# mother_card_19.net
KiCad netlist of a schematic drawn in EAGLE
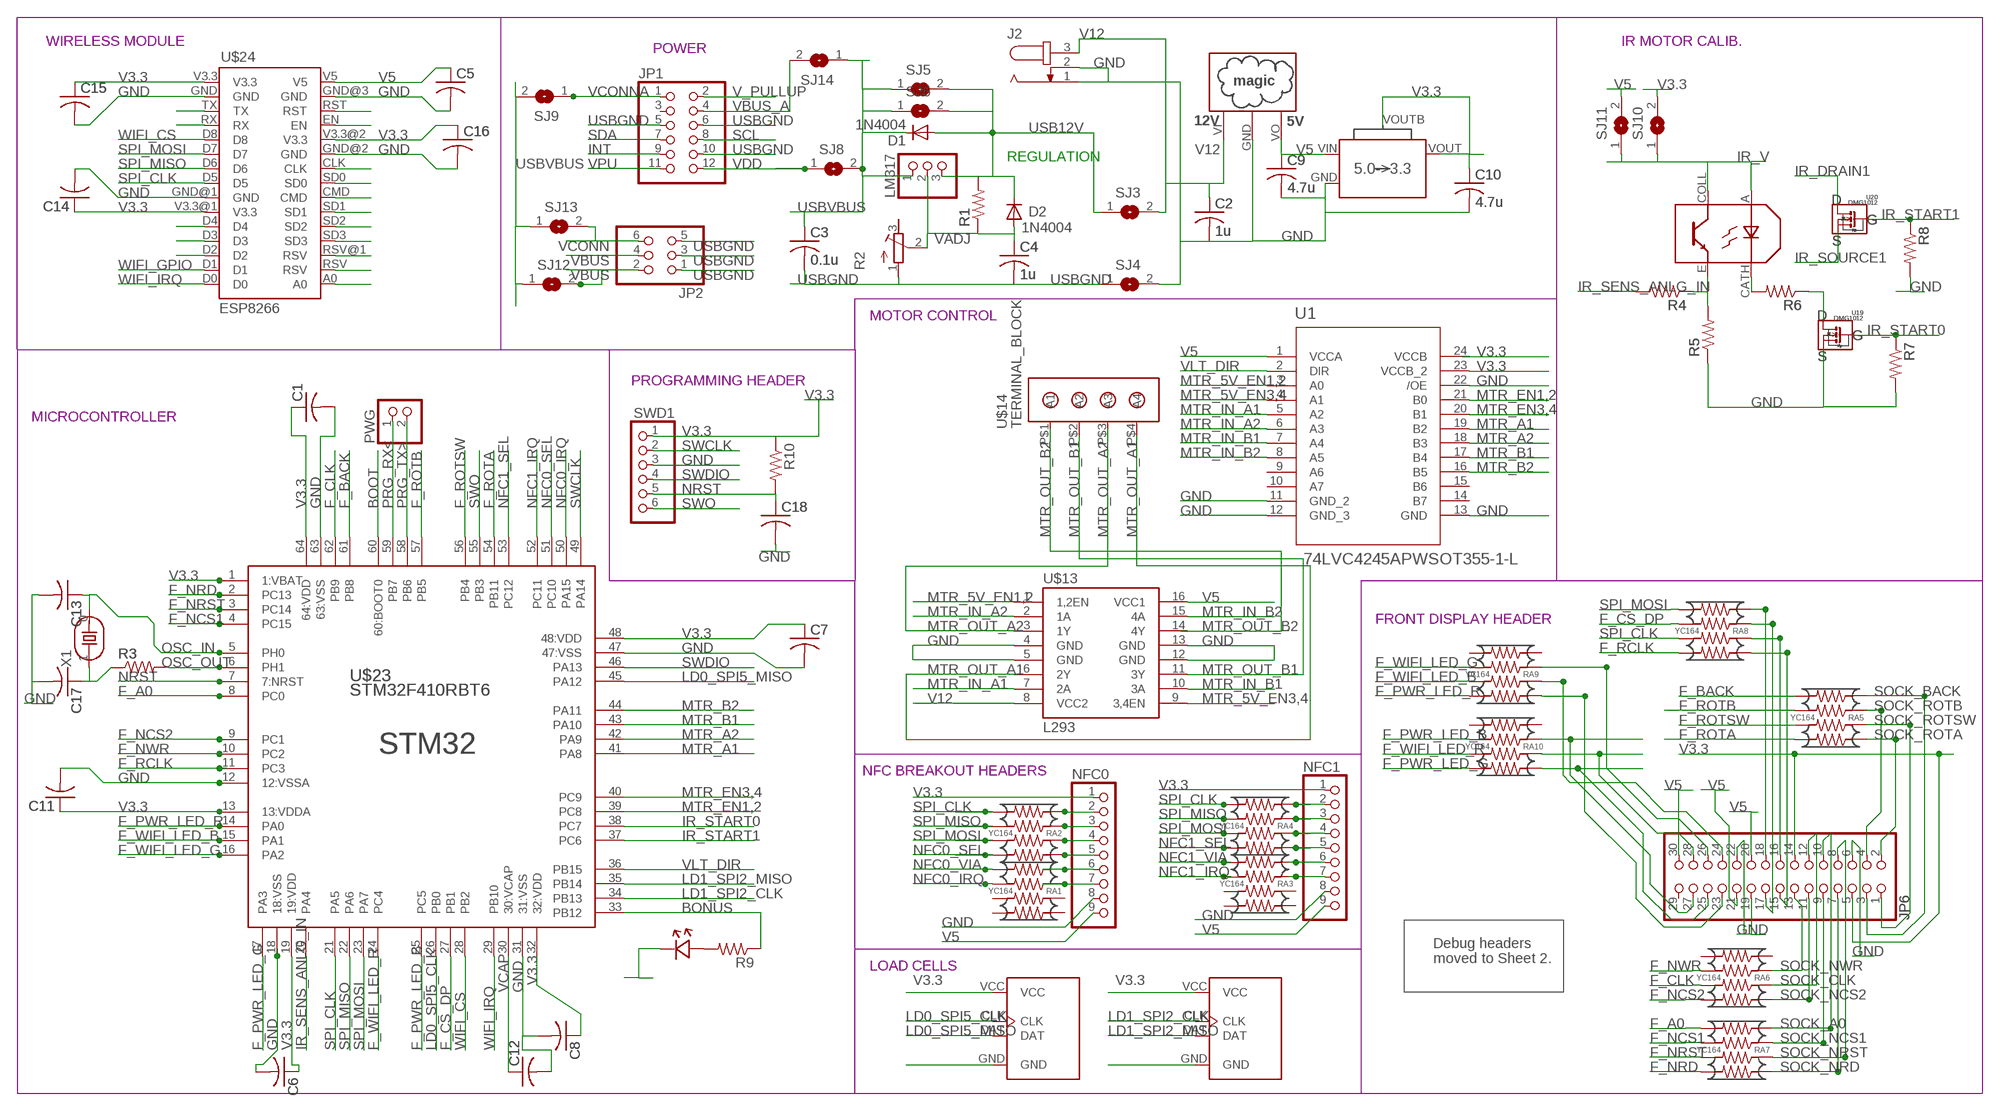
[diagram p0: schematic, sheet 1]
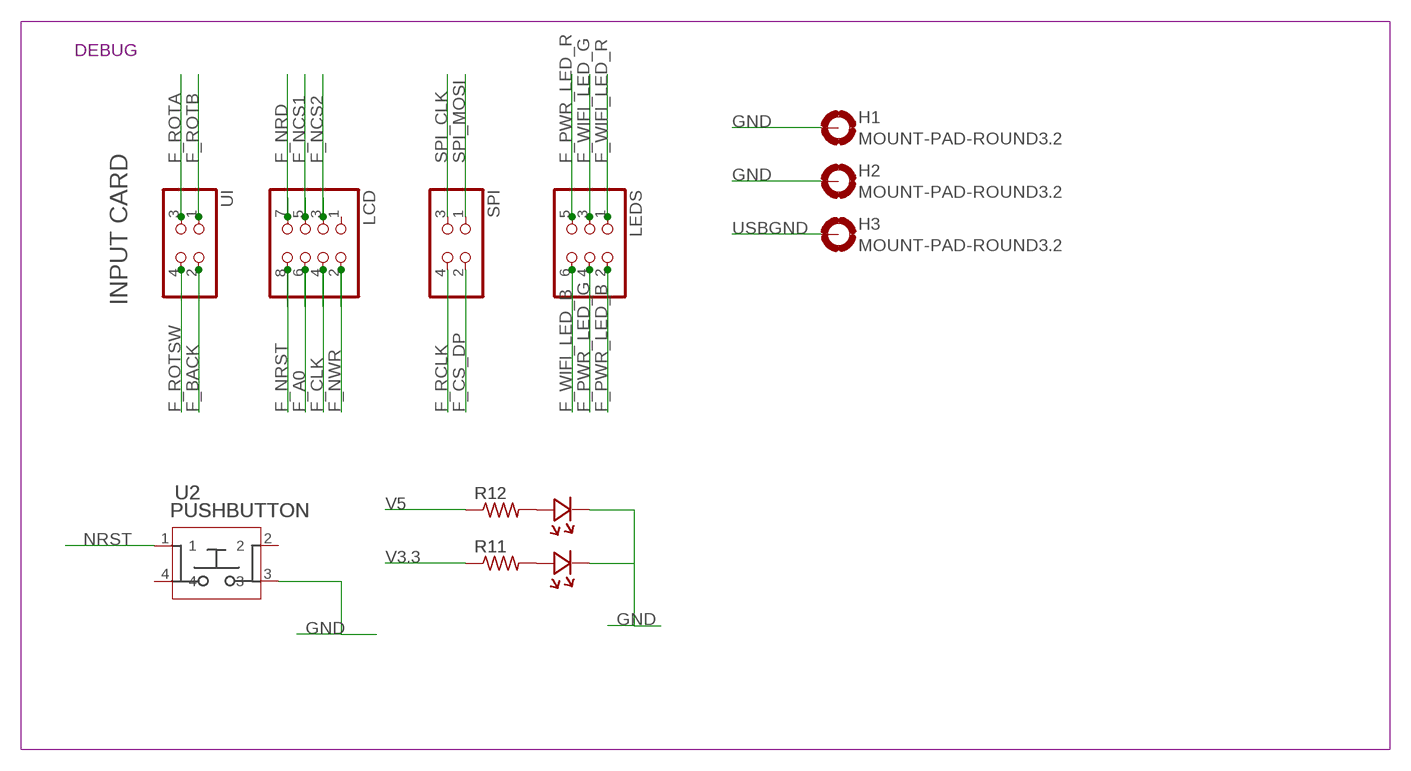
[diagram p1: schematic, sheet 2]

(export (version "E")
  (design (tool "Eeschema 10.0.6"))
  (components
    (comp (ref "C1")
      (value "C-USC0805")
      (footprint "eagle-import:C0805")
      (libsource (lib "eagle-import") (part "C-USC0805"))
    )
    (comp (ref "C2")
      (value "1u")
      (footprint "eagle-import:C0805")
      (libsource (lib "eagle-import") (part "C-USC0805"))
    )
    (comp (ref "C3")
      (value "0.1u")
      (footprint "eagle-import:C0805")
      (libsource (lib "eagle-import") (part "C-USC0805"))
    )
    (comp (ref "C4")
      (value "1u")
      (footprint "eagle-import:C0805")
      (libsource (lib "eagle-import") (part "C-USC0805"))
    )
    (comp (ref "C5")
      (value "C-USC0805")
      (footprint "eagle-import:C0805")
      (libsource (lib "eagle-import") (part "C-USC0805"))
    )
    (comp (ref "C6")
      (value "C-USC0805")
      (footprint "eagle-import:C0805")
      (libsource (lib "eagle-import") (part "C-USC0805"))
    )
    (comp (ref "C7")
      (value "C-USC0805")
      (footprint "eagle-import:C0805")
      (libsource (lib "eagle-import") (part "C-USC0805"))
    )
    (comp (ref "C8")
      (value "C-USC0805")
      (footprint "eagle-import:C0805")
      (libsource (lib "eagle-import") (part "C-USC0805"))
    )
    (comp (ref "C9")
      (value "4.7u")
      (footprint "eagle-import:C0805")
      (libsource (lib "eagle-import") (part "C-USC0805"))
    )
    (comp (ref "C10")
      (value "4.7u")
      (footprint "eagle-import:C0805")
      (libsource (lib "eagle-import") (part "C-USC0805"))
    )
    (comp (ref "C11")
      (value "C-USC0805")
      (footprint "eagle-import:C0805")
      (libsource (lib "eagle-import") (part "C-USC0805"))
    )
    (comp (ref "C12")
      (value "C-USC0805")
      (footprint "eagle-import:C0805")
      (libsource (lib "eagle-import") (part "C-USC0805"))
    )
    (comp (ref "C13")
      (value "C-USC0603")
      (footprint "eagle-import:C0603")
      (libsource (lib "eagle-import") (part "C-USC0603"))
    )
    (comp (ref "C14")
      (value "C-USC0805")
      (footprint "eagle-import:C0805")
      (libsource (lib "eagle-import") (part "C-USC0805"))
    )
    (comp (ref "C15")
      (value "C-USC0805")
      (footprint "eagle-import:C0805")
      (libsource (lib "eagle-import") (part "C-USC0805"))
    )
    (comp (ref "C16")
      (value "C-USC0805")
      (footprint "eagle-import:C0805")
      (libsource (lib "eagle-import") (part "C-USC0805"))
    )
    (comp (ref "C17")
      (value "C-USC0603")
      (footprint "eagle-import:C0603")
      (libsource (lib "eagle-import") (part "C-USC0603"))
    )
    (comp (ref "C18")
      (value "C-USC0805")
      (footprint "eagle-import:C0805")
      (libsource (lib "eagle-import") (part "C-USC0805"))
    )
    (comp (ref "D1")
      (value "1N4004")
      (footprint "eagle-import:DO41-10")
      (libsource (lib "eagle-import") (part "1N4004"))
    )
    (comp (ref "D2")
      (value "1N4004")
      (footprint "eagle-import:DO41-10")
      (libsource (lib "eagle-import") (part "1N4004"))
    )
    (comp (ref "IRSENS")
      (value "TCRT5000")
      (footprint "eagle-import:TCRT5000")
      (libsource (lib "eagle-import") (part "TCRT5000"))
    )
    (comp (ref "J2")
      (value "JACK-PLUG0")
      (footprint "eagle-import:SPC4077")
      (libsource (lib "eagle-import") (part "JACK-PLUG0"))
    )
    (comp (ref "JP1")
      (value "PINHD-2X6")
      (footprint "eagle-import:2X06")
      (libsource (lib "eagle-import") (part "PINHD-2X6"))
    )
    (comp (ref "JP2")
      (value "PINHD-2X3")
      (footprint "eagle-import:2X03")
      (libsource (lib "eagle-import") (part "PINHD-2X3"))
    )
    (comp (ref "JP6")
      (value "PINHD-2X15/SOCK")
      (footprint "eagle-import:2X15_SOCK")
      (libsource (lib "eagle-import") (part "PINHD-2X15/SOCK"))
    )
    (comp (ref "LM317")
      (value "PINHD-1X3")
      (footprint "eagle-import:1X03")
      (libsource (lib "eagle-import") (part "PINHD-1X3"))
    )
    (comp (ref "NFC0")
      (value "PINHD-1X9/90")
      (footprint "eagle-import:1X09_90")
      (libsource (lib "eagle-import") (part "PINHD-1X9/90"))
    )
    (comp (ref "NFC1")
      (value "PINHD-1X9/90")
      (footprint "eagle-import:1X09_90")
      (libsource (lib "eagle-import") (part "PINHD-1X9/90"))
    )
    (comp (ref "PWG")
      (value "PINHD-1X2")
      (footprint "eagle-import:1X02")
      (libsource (lib "eagle-import") (part "PINHD-1X2"))
    )
    (comp (ref "R1")
      (value "R-US_R0805")
      (footprint "eagle-import:R0805")
      (libsource (lib "eagle-import") (part "seniorDesign_R-US_R0805"))
    )
    (comp (ref "R2")
      (value "R-TRIMM64W")
      (footprint "eagle-import:RTRIM64W")
      (libsource (lib "eagle-import") (part "R-TRIMM64W"))
    )
    (comp (ref "R3")
      (value "R-US_R0805")
      (footprint "eagle-import:R0805")
      (libsource (lib "eagle-import") (part "seniorDesign_R-US_R0805"))
    )
    (comp (ref "R4")
      (value "R-US_R0805")
      (footprint "eagle-import:R0805")
      (libsource (lib "eagle-import") (part "seniorDesign_R-US_R0805"))
    )
    (comp (ref "R5")
      (value "R-US_R0805")
      (footprint "eagle-import:R0805")
      (libsource (lib "eagle-import") (part "seniorDesign_R-US_R0805"))
    )
    (comp (ref "R6")
      (value "R-US_R0805")
      (footprint "eagle-import:R0805")
      (libsource (lib "eagle-import") (part "seniorDesign_R-US_R0805"))
    )
    (comp (ref "R7")
      (value "R-US_R0805")
      (footprint "eagle-import:R0805")
      (libsource (lib "eagle-import") (part "seniorDesign_R-US_R0805"))
    )
    (comp (ref "R8")
      (value "R-US_R0805")
      (footprint "eagle-import:R0805")
      (libsource (lib "eagle-import") (part "seniorDesign_R-US_R0805"))
    )
    (comp (ref "R9")
      (value "R-US_R0805")
      (footprint "eagle-import:R0805")
      (libsource (lib "eagle-import") (part "R-US_R0805"))
    )
    (comp (ref "R10")
      (value "R-US_R0805")
      (footprint "eagle-import:R0805")
      (libsource (lib "eagle-import") (part "R-US_R0805"))
    )
    (comp (ref "RA1")
      (value "YC164")
      (footprint "eagle-import:YC164")
      (libsource (lib "eagle-import") (part "YC164"))
    )
    (comp (ref "RA2")
      (value "YC164")
      (footprint "eagle-import:YC164")
      (libsource (lib "eagle-import") (part "YC164"))
    )
    (comp (ref "RA3")
      (value "YC164")
      (footprint "eagle-import:YC164")
      (libsource (lib "eagle-import") (part "YC164"))
    )
    (comp (ref "RA4")
      (value "YC164")
      (footprint "eagle-import:YC164")
      (libsource (lib "eagle-import") (part "YC164"))
    )
    (comp (ref "RA5")
      (value "YC164")
      (footprint "eagle-import:YC164")
      (libsource (lib "eagle-import") (part "YC164"))
    )
    (comp (ref "RA6")
      (value "YC164")
      (footprint "eagle-import:YC164")
      (libsource (lib "eagle-import") (part "YC164"))
    )
    (comp (ref "RA7")
      (value "YC164")
      (footprint "eagle-import:YC164")
      (libsource (lib "eagle-import") (part "YC164"))
    )
    (comp (ref "RA8")
      (value "YC164")
      (footprint "eagle-import:YC164")
      (libsource (lib "eagle-import") (part "YC164"))
    )
    (comp (ref "RA9")
      (value "YC164")
      (footprint "eagle-import:YC164")
      (libsource (lib "eagle-import") (part "YC164"))
    )
    (comp (ref "RA10")
      (value "YC164")
      (footprint "eagle-import:YC164")
      (libsource (lib "eagle-import") (part "YC164"))
    )
    (comp (ref "SJ3") (value "SJ") (footprint "eagle-import:SJ") (libsource (lib "eagle-import") (part "SJ")))
    (comp (ref "SJ4") (value "SJ") (footprint "eagle-import:SJ") (libsource (lib "eagle-import") (part "SJ")))
    (comp (ref "SJ5") (value "SJ") (footprint "eagle-import:SJ") (libsource (lib "eagle-import") (part "SJ")))
    (comp (ref "SJ6") (value "SJ") (footprint "eagle-import:SJ") (libsource (lib "eagle-import") (part "SJ")))
    (comp (ref "SJ8") (value "SJ") (footprint "eagle-import:SJ") (libsource (lib "eagle-import") (part "SJ")))
    (comp (ref "SJ9") (value "SJ") (footprint "eagle-import:SJ") (libsource (lib "eagle-import") (part "SJ")))
    (comp (ref "SJ10")
      (value "SJ")
      (footprint "eagle-import:SJ")
      (libsource (lib "eagle-import") (part "SJ"))
    )
    (comp (ref "SJ11")
      (value "SJ")
      (footprint "eagle-import:SJ")
      (libsource (lib "eagle-import") (part "SJ"))
    )
    (comp (ref "SJ12")
      (value "SJ")
      (footprint "eagle-import:SJ")
      (libsource (lib "eagle-import") (part "SJ"))
    )
    (comp (ref "SJ13")
      (value "SJ")
      (footprint "eagle-import:SJ")
      (libsource (lib "eagle-import") (part "SJ"))
    )
    (comp (ref "SJ14")
      (value "SJ")
      (footprint "eagle-import:SJ")
      (libsource (lib "eagle-import") (part "SJ"))
    )
    (comp (ref "SWD1")
      (value "PINHD-1X6")
      (footprint "eagle-import:1X06")
      (libsource (lib "eagle-import") (part "PINHD-1X6"))
    )
    (comp (ref "U$1")
      (value "LED0603")
      (footprint "eagle-import:LED")
      (libsource (lib "eagle-import") (part "LED0603"))
    )
    (comp (ref "U$13")
      (value "L293")
      (footprint "eagle-import:DIL16")
      (libsource (lib "eagle-import") (part "L293"))
    )
    (comp (ref "U$14")
      (value "TERMINAL_BLOCK")
      (footprint "eagle-import:1X4_BLOCK")
      (libsource (lib "eagle-import") (part "TERMINAL_BLOCK"))
    )
    (comp (ref "U$15")
      (value "AP2114H")
      (footprint "eagle-import:AP2114H")
      (libsource (lib "eagle-import") (part "AP2114H"))
    )
    (comp (ref "U$16")
      (value "OKI-78SR-W36")
      (footprint "eagle-import:SIP3")
      (libsource (lib "eagle-import") (part "OKI-78SR-W36"))
    )
    (comp (ref "U$21")
      (value "HX711")
      (footprint "eagle-import:HX711")
      (libsource (lib "eagle-import") (part "HX711"))
    )
    (comp (ref "U$22")
      (value "HX711")
      (footprint "eagle-import:HX711")
      (libsource (lib "eagle-import") (part "HX711"))
    )
    (comp (ref "U$23")
      (value "STM32F410RBT6")
      (footprint "eagle-import:QFP50P1200X1200X160-64N")
      (libsource (lib "eagle-import") (part "STM32F410RBT6"))
    )
    (comp (ref "U$24")
      (value "ESP8266")
      (footprint "eagle-import:ESP8266")
      (libsource (lib "eagle-import") (part "ESP8266"))
    )
    (comp (ref "U1")
      (value "74LVC4245APWSOT355-1-L")
      (footprint "eagle-import:SOT355-1-L")
      (fields (field (name "MANUFACTURER_PART_NUMBER") "74LVC4245APW"))
      (libsource (lib "eagle-import") (part "74LVC4245APWSOT355-1-L"))
    )
    (comp (ref "U19")
      (value "DMG1012")
      (footprint "eagle-import:SOT323")
      (libsource (lib "eagle-import") (part "DMG1012"))
    )
    (comp (ref "U20")
      (value "DMG1012")
      (footprint "eagle-import:SOT323")
      (libsource (lib "eagle-import") (part "DMG1012"))
    )
    (comp (ref "X1")
      (value "HC-49S_9B")
      (footprint "eagle-import:HC-49S_9B")
      (libsource (lib "eagle-import") (part "HC-49S_9B"))
    )
    (comp (ref "H1")
      (value "MOUNT-PAD-ROUND3.2")
      (footprint "eagle-import:3,2-PAD")
      (libsource (lib "eagle-import") (part "MOUNT-PAD-ROUND3.2"))
    )
    (comp (ref "H2")
      (value "MOUNT-PAD-ROUND3.2")
      (footprint "eagle-import:3,2-PAD")
      (libsource (lib "eagle-import") (part "MOUNT-PAD-ROUND3.2"))
    )
    (comp (ref "H3")
      (value "MOUNT-PAD-ROUND3.2")
      (footprint "eagle-import:3,2-PAD")
      (libsource (lib "eagle-import") (part "MOUNT-PAD-ROUND3.2"))
    )
    (comp (ref "LCD")
      (value "PINHD-2X4")
      (footprint "eagle-import:2X04")
      (libsource (lib "eagle-import") (part "PINHD-2X4"))
    )
    (comp (ref "LEDS")
      (value "PINHD-2X3")
      (footprint "eagle-import:2X03")
      (libsource (lib "eagle-import") (part "PINHD-2X3"))
    )
    (comp (ref "R11")
      (value "R-US_R0805")
      (footprint "eagle-import:R0805")
      (libsource (lib "eagle-import") (part "seniorDesign_R-US_R0805"))
    )
    (comp (ref "R12")
      (value "R-US_R0805")
      (footprint "eagle-import:R0805")
      (libsource (lib "eagle-import") (part "seniorDesign_R-US_R0805"))
    )
    (comp (ref "SPI")
      (value "PINHD-2X2")
      (footprint "eagle-import:2X02")
      (libsource (lib "eagle-import") (part "PINHD-2X2"))
    )
    (comp (ref "U$2")
      (value "LED0603")
      (footprint "eagle-import:LED")
      (libsource (lib "eagle-import") (part "LED0603"))
    )
    (comp (ref "U$3")
      (value "LED0603")
      (footprint "eagle-import:LED")
      (libsource (lib "eagle-import") (part "LED0603"))
    )
    (comp (ref "U2")
      (value "PUSHBUTTON")
      (footprint "eagle-import:SWITCH_FSM14JH")
      (fields (field (name "MANUFACTURER_PART_NUMBER") "218259107"))
      (libsource (lib "eagle-import") (part "PUSHBUTTON"))
    )
    (comp (ref "UI")
      (value "PINHD-2X2")
      (footprint "eagle-import:2X02")
      (libsource (lib "eagle-import") (part "PINHD-2X2"))
    )
  )
  (nets
    (net (code "1") (name "BONUS") (class "Default")
      (node (ref "R9") (pin "1") (pinfunction "1_1") (pintype "passive"))
      (node (ref "U$23") (pin "33") (pinfunction "PB12_33") (pintype "bidirectional"))
    )
    (net (code "2") (name "BOOT") (class "Default")
      (node (ref "U$23") (pin "60") (pinfunction "60:BOOT0_60") (pintype "bidirectional"))
    )
    (net (code "3") (name "F_A0") (class "Default")
      (node (ref "LCD") (pin "6") (pinfunction "6_6") (pintype "passive"))
      (node (ref "RA7") (pin "P$4") (pinfunction "4_P$4") (pintype "passive"))
      (node (ref "U$23") (pin "8") (pinfunction "PC0_8") (pintype "bidirectional"))
    )
    (net (code "4") (name "F_BACK") (class "Default")
      (node (ref "RA5") (pin "P$4") (pinfunction "4_P$4") (pintype "passive"))
      (node (ref "U$23") (pin "61") (pinfunction "PB8_61") (pintype "bidirectional"))
      (node (ref "UI") (pin "2") (pinfunction "2_2") (pintype "passive"))
    )
    (net (code "5") (name "F_CLK") (class "Default")
      (node (ref "LCD") (pin "4") (pinfunction "4_4") (pintype "passive"))
      (node (ref "RA6") (pin "P$2") (pinfunction "2_P$2") (pintype "passive"))
      (node (ref "U$23") (pin "62") (pinfunction "PB9_62") (pintype "bidirectional"))
    )
    (net (code "6") (name "F_CS_DP") (class "Default")
      (node (ref "RA8") (pin "P$3") (pinfunction "3_P$3") (pintype "passive"))
      (node (ref "SPI") (pin "2") (pinfunction "2_2") (pintype "passive"))
      (node (ref "U$23") (pin "27") (pinfunction "PB1_27") (pintype "bidirectional"))
    )
    (net (code "7") (name "F_NCS1") (class "Default")
      (node (ref "LCD") (pin "5") (pinfunction "5_5") (pintype "passive"))
      (node (ref "RA7") (pin "P$3") (pinfunction "3_P$3") (pintype "passive"))
      (node (ref "U$23") (pin "4") (pinfunction "PC15_4") (pintype "bidirectional"))
    )
    (net (code "8") (name "F_NCS2") (class "Default")
      (node (ref "LCD") (pin "3") (pinfunction "3_3") (pintype "passive"))
      (node (ref "RA6") (pin "P$1") (pinfunction "1_P$1") (pintype "passive"))
      (node (ref "U$23") (pin "9") (pinfunction "PC1_9") (pintype "bidirectional"))
    )
    (net (code "9") (name "F_NRD") (class "Default")
      (node (ref "LCD") (pin "7") (pinfunction "7_7") (pintype "passive"))
      (node (ref "RA7") (pin "P$1") (pinfunction "1_P$1") (pintype "passive"))
      (node (ref "U$23") (pin "2") (pinfunction "PC13_2") (pintype "bidirectional"))
    )
    (net (code "10") (name "F_NRST") (class "Default")
      (node (ref "LCD") (pin "8") (pinfunction "8_8") (pintype "passive"))
      (node (ref "RA7") (pin "P$2") (pinfunction "2_P$2") (pintype "passive"))
      (node (ref "U$23") (pin "3") (pinfunction "PC14_3") (pintype "bidirectional"))
    )
    (net (code "11") (name "F_NWR") (class "Default")
      (node (ref "LCD") (pin "2") (pinfunction "2_2") (pintype "passive"))
      (node (ref "RA6") (pin "P$3") (pinfunction "3_P$3") (pintype "passive"))
      (node (ref "U$23") (pin "10") (pinfunction "PC2_10") (pintype "bidirectional"))
    )
    (net (code "12") (name "F_PWR_LED_B") (class "Default")
      (node (ref "LEDS") (pin "2") (pinfunction "2_2") (pintype "passive"))
      (node (ref "RA10") (pin "P$3") (pinfunction "3_P$3") (pintype "passive"))
      (node (ref "U$23") (pin "25") (pinfunction "PC5_25") (pintype "bidirectional"))
    )
    (net (code "13") (name "F_PWR_LED_G") (class "Default")
      (node (ref "LEDS") (pin "4") (pinfunction "4_4") (pintype "passive"))
      (node (ref "RA10") (pin "P$1") (pinfunction "1_P$1") (pintype "passive"))
      (node (ref "U$23") (pin "17") (pinfunction "PA3_17") (pintype "bidirectional"))
    )
    (net (code "14") (name "F_PWR_LED_R") (class "Default")
      (node (ref "LEDS") (pin "5") (pinfunction "5_5") (pintype "passive"))
      (node (ref "RA9") (pin "P$1") (pinfunction "1_P$1") (pintype "passive"))
      (node (ref "U$23") (pin "14") (pinfunction "PA0_14") (pintype "bidirectional"))
    )
    (net (code "15") (name "F_RCLK") (class "Default")
      (node (ref "RA8") (pin "P$1") (pinfunction "1_P$1") (pintype "passive"))
      (node (ref "SPI") (pin "4") (pinfunction "4_4") (pintype "passive"))
      (node (ref "U$23") (pin "11") (pinfunction "PC3_11") (pintype "bidirectional"))
    )
    (net (code "16") (name "F_ROTA") (class "Default")
      (node (ref "RA5") (pin "P$1") (pinfunction "1_P$1") (pintype "passive"))
      (node (ref "U$23") (pin "54") (pinfunction "PB11_54") (pintype "bidirectional"))
      (node (ref "UI") (pin "3") (pinfunction "3_3") (pintype "passive"))
    )
    (net (code "17") (name "F_ROTB") (class "Default")
      (node (ref "RA5") (pin "P$3") (pinfunction "3_P$3") (pintype "passive"))
      (node (ref "U$23") (pin "57") (pinfunction "PB5_57") (pintype "bidirectional"))
      (node (ref "UI") (pin "1") (pinfunction "1_1") (pintype "passive"))
    )
    (net (code "18") (name "F_ROTSW") (class "Default")
      (node (ref "RA5") (pin "P$2") (pinfunction "2_P$2") (pintype "passive"))
      (node (ref "U$23") (pin "56") (pinfunction "PB4_56") (pintype "bidirectional"))
      (node (ref "UI") (pin "4") (pinfunction "4_4") (pintype "passive"))
    )
    (net (code "19") (name "F_WIFI_LED_B") (class "Default")
      (node (ref "LEDS") (pin "6") (pinfunction "6_6") (pintype "passive"))
      (node (ref "RA9") (pin "P$2") (pinfunction "2_P$2") (pintype "passive"))
      (node (ref "U$23") (pin "15") (pinfunction "PA1_15") (pintype "bidirectional"))
    )
    (net (code "20") (name "F_WIFI_LED_G") (class "Default")
      (node (ref "LEDS") (pin "3") (pinfunction "3_3") (pintype "passive"))
      (node (ref "RA9") (pin "P$3") (pinfunction "3_P$3") (pintype "passive"))
      (node (ref "U$23") (pin "16") (pinfunction "PA2_16") (pintype "bidirectional"))
    )
    (net (code "21") (name "F_WIFI_LED_R") (class "Default")
      (node (ref "LEDS") (pin "1") (pinfunction "1_1") (pintype "passive"))
      (node (ref "RA10") (pin "P$2") (pinfunction "2_P$2") (pintype "passive"))
      (node (ref "U$23") (pin "24") (pinfunction "PC4_24") (pintype "bidirectional"))
    )
    (net (code "22") (name "GND") (class "Default")
      (node (ref "C1") (pin "2") (pinfunction "2_2") (pintype "passive"))
      (node (ref "C10") (pin "2") (pinfunction "2_2") (pintype "passive"))
      (node (ref "C11") (pin "2") (pinfunction "2_2") (pintype "passive"))
      (node (ref "C12") (pin "2") (pinfunction "2_2") (pintype "passive"))
      (node (ref "C13") (pin "2") (pinfunction "2_2") (pintype "passive"))
      (node (ref "C14") (pin "2") (pinfunction "2_2") (pintype "passive"))
      (node (ref "C15") (pin "2") (pinfunction "2_2") (pintype "passive"))
      (node (ref "C16") (pin "2") (pinfunction "2_2") (pintype "passive"))
      (node (ref "C17") (pin "2") (pinfunction "2_2") (pintype "passive"))
      (node (ref "C18") (pin "2") (pinfunction "2_2") (pintype "passive"))
      (node (ref "C2") (pin "2") (pinfunction "2_2") (pintype "passive"))
      (node (ref "C5") (pin "2") (pinfunction "2_2") (pintype "passive"))
      (node (ref "C6") (pin "2") (pinfunction "2_2") (pintype "passive"))
      (node (ref "C7") (pin "2") (pinfunction "2_2") (pintype "passive"))
      (node (ref "C8") (pin "2") (pinfunction "2_2") (pintype "passive"))
      (node (ref "C9") (pin "2") (pinfunction "2_2") (pintype "passive"))
      (node (ref "H1") (pin "B3,2") (pinfunction "MOUNT_B3,2") (pintype "passive"))
      (node (ref "H2") (pin "B3,2") (pinfunction "MOUNT_B3,2") (pintype "passive"))
      (node (ref "J2") (pin "1") (pinfunction "1_1") (pintype "passive"))
      (node (ref "J2") (pin "2") (pinfunction "2_2") (pintype "passive"))
      (node (ref "JP6") (pin "19") (pinfunction "19_19") (pintype "passive"))
      (node (ref "JP6") (pin "22") (pinfunction "22_22") (pintype "passive"))
      (node (ref "JP6") (pin "6") (pinfunction "6_6") (pintype "passive"))
      (node (ref "NFC0") (pin "8") (pinfunction "8_8") (pintype "passive"))
      (node (ref "NFC1") (pin "8") (pinfunction "8_8") (pintype "passive"))
      (node (ref "R5") (pin "1") (pinfunction "1_1") (pintype "passive"))
      (node (ref "R7") (pin "2") (pinfunction "2_2") (pintype "passive"))
      (node (ref "R8") (pin "2") (pinfunction "2_2") (pintype "passive"))
      (node (ref "SJ4") (pin "2") (pinfunction "2_2") (pintype "passive"))
      (node (ref "SWD1") (pin "3") (pinfunction "3_3") (pintype "passive"))
      (node (ref "U$13") (pin "12") (pinfunction "GND_12") (pintype "bidirectional"))
      (node (ref "U$13") (pin "13") (pinfunction "GND_13") (pintype "bidirectional"))
      (node (ref "U$13") (pin "4") (pinfunction "GND_4") (pintype "bidirectional"))
      (node (ref "U$13") (pin "5") (pinfunction "GND_5") (pintype "bidirectional"))
      (node (ref "U$15") (pin "GND") (pinfunction "GND_GND") (pintype "power_in"))
      (node (ref "U$16") (pin "GND") (pinfunction "P$2_GND") (pintype "power_in"))
      (node (ref "U$2") (pin "CATHODE") (pinfunction "CA_CATHODE") (pintype "output"))
      (node (ref "U$21") (pin "GND") (pinfunction "GND_GND") (pintype "power_in"))
      (node (ref "U$22") (pin "GND") (pinfunction "GND_GND") (pintype "power_in"))
      (node (ref "U$23") (pin "12") (pinfunction "12:VSSA_12") (pintype "bidirectional"))
      (node (ref "U$23") (pin "18") (pinfunction "18:VSS_18") (pintype "bidirectional"))
      (node (ref "U$23") (pin "31") (pinfunction "31:VSS_31") (pintype "bidirectional"))
      (node (ref "U$23") (pin "47") (pinfunction "47:VSS_47") (pintype "bidirectional"))
      (node (ref "U$23") (pin "63") (pinfunction "63:VSS_63") (pintype "bidirectional"))
      (node (ref "U$24") (pin "GND") (pinfunction "GND_GND") (pintype "bidirectional"))
      (node (ref "U$24") (pin "GND@1") (pinfunction "GND_GND@1") (pintype "bidirectional"))
      (node (ref "U$24") (pin "GND@2") (pinfunction "GND_GND@2") (pintype "bidirectional"))
      (node (ref "U$24") (pin "GND@3") (pinfunction "GND_GND@3") (pintype "bidirectional"))
      (node (ref "U$3") (pin "CATHODE") (pinfunction "CA_CATHODE") (pintype "output"))
      (node (ref "U1") (pin "11") (pinfunction "GND_2_11") (pintype "power_in"))
      (node (ref "U1") (pin "12") (pinfunction "GND_3_12") (pintype "power_in"))
      (node (ref "U1") (pin "13") (pinfunction "GND_13") (pintype "power_in"))
      (node (ref "U1") (pin "22") (pinfunction "/OE_22") (pintype "input"))
      (node (ref "U19") (pin "S") (pinfunction "S_S") (pintype "bidirectional"))
      (node (ref "U2") (pin "3") (pinfunction "3_3") (pintype "passive"))
    )
    (net (code "23") (name "INT") (class "Default")
      (node (ref "JP1") (pin "9") (pinfunction "9_9") (pintype "passive"))
    )
    (net (code "24") (name "IR_DRAIN1") (class "Default")
      (node (ref "U20") (pin "D") (pinfunction "D_D") (pintype "bidirectional"))
    )
    (net (code "25") (name "IR_SENS_ANLG_IN") (class "Default")
      (node (ref "R4") (pin "2") (pinfunction "2_2") (pintype "passive"))
      (node (ref "U$23") (pin "20") (pinfunction "PA4_20") (pintype "bidirectional"))
    )
    (net (code "26") (name "IR_SOURCE1") (class "Default")
      (node (ref "U20") (pin "S") (pinfunction "S_S") (pintype "bidirectional"))
    )
    (net (code "27") (name "IR_START0") (class "Default")
      (node (ref "R7") (pin "1") (pinfunction "1_1") (pintype "passive"))
      (node (ref "U$23") (pin "38") (pinfunction "PC7_38") (pintype "bidirectional"))
      (node (ref "U19") (pin "G") (pinfunction "G_G") (pintype "bidirectional"))
    )
    (net (code "28") (name "IR_START1") (class "Default")
      (node (ref "R8") (pin "1") (pinfunction "1_1") (pintype "passive"))
      (node (ref "U$23") (pin "37") (pinfunction "PC6_37") (pintype "bidirectional"))
      (node (ref "U20") (pin "G") (pinfunction "G_G") (pintype "bidirectional"))
    )
    (net (code "29") (name "IR_V") (class "Default")
      (node (ref "IRSENS") (pin "A") (pinfunction "A_A") (pintype "bidirectional"))
      (node (ref "IRSENS") (pin "COLL") (pinfunction "COLL_COLL") (pintype "bidirectional"))
      (node (ref "SJ10") (pin "1") (pinfunction "1_1") (pintype "passive"))
      (node (ref "SJ11") (pin "1") (pinfunction "1_1") (pintype "passive"))
    )
    (net (code "30") (name "LD0_SPI5_CLK") (class "Default")
      (node (ref "U$21") (pin "CLK") (pinfunction "CLK_CLK") (pintype "bidirectional"))
      (node (ref "U$23") (pin "26") (pinfunction "PB0_26") (pintype "bidirectional"))
    )
    (net (code "31") (name "LD0_SPI5_MISO") (class "Default")
      (node (ref "U$21") (pin "DAT") (pinfunction "DAT_DAT") (pintype "bidirectional"))
      (node (ref "U$23") (pin "45") (pinfunction "PA12_45") (pintype "bidirectional"))
    )
    (net (code "32") (name "LD1_SPI2_CLK") (class "Default")
      (node (ref "U$22") (pin "CLK") (pinfunction "CLK_CLK") (pintype "bidirectional"))
      (node (ref "U$23") (pin "34") (pinfunction "PB13_34") (pintype "bidirectional"))
    )
    (net (code "33") (name "LD1_SPI2_MISO") (class "Default")
      (node (ref "U$22") (pin "DAT") (pinfunction "DAT_DAT") (pintype "bidirectional"))
      (node (ref "U$23") (pin "35") (pinfunction "PB14_35") (pintype "bidirectional"))
    )
    (net (code "34") (name "MTR_5V_EN1,2") (class "Default")
      (node (ref "U$13") (pin "1") (pinfunction "1,2EN_1") (pintype "bidirectional"))
      (node (ref "U1") (pin "3") (pinfunction "A0_3") (pintype "bidirectional"))
    )
    (net (code "35") (name "MTR_5V_EN3,4") (class "Default")
      (node (ref "U$13") (pin "9") (pinfunction "3,4EN_9") (pintype "bidirectional"))
      (node (ref "U1") (pin "4") (pinfunction "A1_4") (pintype "bidirectional"))
    )
    (net (code "36") (name "MTR_A1") (class "Default")
      (node (ref "U$23") (pin "41") (pinfunction "PA8_41") (pintype "bidirectional"))
      (node (ref "U1") (pin "19") (pinfunction "B2_19") (pintype "bidirectional"))
    )
    (net (code "37") (name "MTR_A2") (class "Default")
      (node (ref "U$23") (pin "42") (pinfunction "PA9_42") (pintype "bidirectional"))
      (node (ref "U1") (pin "18") (pinfunction "B3_18") (pintype "bidirectional"))
    )
    (net (code "38") (name "MTR_B1") (class "Default")
      (node (ref "U$23") (pin "43") (pinfunction "PA10_43") (pintype "bidirectional"))
      (node (ref "U1") (pin "17") (pinfunction "B4_17") (pintype "bidirectional"))
    )
    (net (code "39") (name "MTR_B2") (class "Default")
      (node (ref "U$23") (pin "44") (pinfunction "PA11_44") (pintype "bidirectional"))
      (node (ref "U1") (pin "16") (pinfunction "B5_16") (pintype "bidirectional"))
    )
    (net (code "40") (name "MTR_EN1,2") (class "Default")
      (node (ref "U$23") (pin "39") (pinfunction "PC8_39") (pintype "bidirectional"))
      (node (ref "U1") (pin "21") (pinfunction "B0_21") (pintype "bidirectional"))
    )
    (net (code "41") (name "MTR_EN3,4") (class "Default")
      (node (ref "U$23") (pin "40") (pinfunction "PC9_40") (pintype "bidirectional"))
      (node (ref "U1") (pin "20") (pinfunction "B1_20") (pintype "bidirectional"))
    )
    (net (code "42") (name "MTR_IN_A1") (class "Default")
      (node (ref "U$13") (pin "7") (pinfunction "2A_7") (pintype "bidirectional"))
      (node (ref "U1") (pin "5") (pinfunction "A2_5") (pintype "bidirectional"))
    )
    (net (code "43") (name "MTR_IN_A2") (class "Default")
      (node (ref "U$13") (pin "2") (pinfunction "1A_2") (pintype "bidirectional"))
      (node (ref "U1") (pin "6") (pinfunction "A3_6") (pintype "bidirectional"))
    )
    (net (code "44") (name "MTR_IN_B1") (class "Default")
      (node (ref "U$13") (pin "10") (pinfunction "3A_10") (pintype "bidirectional"))
      (node (ref "U1") (pin "7") (pinfunction "A4_7") (pintype "bidirectional"))
    )
    (net (code "45") (name "MTR_IN_B2") (class "Default")
      (node (ref "U$13") (pin "15") (pinfunction "4A_15") (pintype "bidirectional"))
      (node (ref "U1") (pin "8") (pinfunction "A5_8") (pintype "bidirectional"))
    )
    (net (code "46") (name "MTR_OUT_A1") (class "Default")
      (node (ref "U$13") (pin "6") (pinfunction "2Y_6") (pintype "bidirectional"))
      (node (ref "U$14") (pin "P$4") (pinfunction "A4_P$4") (pintype "bidirectional"))
    )
    (net (code "47") (name "MTR_OUT_A2") (class "Default")
      (node (ref "U$13") (pin "3") (pinfunction "1Y_3") (pintype "bidirectional"))
      (node (ref "U$14") (pin "P$3") (pinfunction "A3_P$3") (pintype "bidirectional"))
    )
    (net (code "48") (name "MTR_OUT_B1") (class "Default")
      (node (ref "U$13") (pin "11") (pinfunction "3Y_11") (pintype "bidirectional"))
      (node (ref "U$14") (pin "P$2") (pinfunction "A2_P$2") (pintype "bidirectional"))
    )
    (net (code "49") (name "MTR_OUT_B2") (class "Default")
      (node (ref "U$13") (pin "14") (pinfunction "4Y_14") (pintype "bidirectional"))
      (node (ref "U$14") (pin "P$1") (pinfunction "A1_P$1") (pintype "bidirectional"))
    )
    (net (code "50") (name "NFC0_IRQ") (class "Default")
      (node (ref "RA1") (pin "P$3") (pinfunction "3_P$3") (pintype "passive"))
      (node (ref "U$23") (pin "50") (pinfunction "PA15_50") (pintype "bidirectional"))
    )
    (net (code "51") (name "NFC0_SEL") (class "Default")
      (node (ref "RA2") (pin "P$1") (pinfunction "1_P$1") (pintype "passive"))
      (node (ref "U$23") (pin "51") (pinfunction "PC10_51") (pintype "bidirectional"))
    )
    (net (code "52") (name "NFC0_VIA") (class "Default")
      (node (ref "RA1") (pin "P$4") (pinfunction "4_P$4") (pintype "passive"))
    )
    (net (code "53") (name "NFC1_IRQ") (class "Default")
      (node (ref "RA3") (pin "P$3") (pinfunction "3_P$3") (pintype "passive"))
      (node (ref "U$23") (pin "52") (pinfunction "PC11_52") (pintype "bidirectional"))
    )
    (net (code "54") (name "NFC1_SEL") (class "Default")
      (node (ref "RA4") (pin "P$1") (pinfunction "1_P$1") (pintype "passive"))
      (node (ref "U$23") (pin "53") (pinfunction "PC12_53") (pintype "bidirectional"))
    )
    (net (code "55") (name "NFC1_VIA") (class "Default")
      (node (ref "RA3") (pin "P$4") (pinfunction "4_P$4") (pintype "passive"))
    )
    (net (code "56") (name "NRST") (class "Default")
      (node (ref "C18") (pin "1") (pinfunction "1_1") (pintype "passive"))
      (node (ref "R10") (pin "2") (pinfunction "2_2") (pintype "passive"))
      (node (ref "SWD1") (pin "5") (pinfunction "5_5") (pintype "passive"))
      (node (ref "U$23") (pin "7") (pinfunction "7:NRST_7") (pintype "bidirectional"))
      (node (ref "U2") (pin "1") (pinfunction "1_1") (pintype "passive"))
    )
    (net (code "57") (name "Net-(IRSENS-PadCATH)") (class "Default")
      (node (ref "IRSENS") (pin "CATH") (pinfunction "CATH_CATH") (pintype "bidirectional"))
      (node (ref "R6") (pin "2") (pinfunction "2_2") (pintype "passive"))
    )
    (net (code "58") (name "Net-(IRSENS-PadE)") (class "Default")
      (node (ref "IRSENS") (pin "E") (pinfunction "E_E") (pintype "bidirectional"))
      (node (ref "R4") (pin "1") (pinfunction "1_1") (pintype "passive"))
      (node (ref "R5") (pin "2") (pinfunction "2_2") (pintype "passive"))
    )
    (net (code "59") (name "Net-(R6-Pad1)") (class "Default")
      (node (ref "R6") (pin "1") (pinfunction "1_1") (pintype "passive"))
      (node (ref "U19") (pin "D") (pinfunction "D_D") (pintype "bidirectional"))
    )
    (net (code "60") (name "Net-(RA1-33)") (class "Default")
      (node (ref "NFC0") (pin "7") (pinfunction "7_7") (pintype "passive"))
      (node (ref "RA1") (pin "P$33") (pinfunction "33_P$33") (pintype "passive"))
    )
    (net (code "61") (name "Net-(RA1-44)") (class "Default")
      (node (ref "NFC0") (pin "6") (pinfunction "6_6") (pintype "passive"))
      (node (ref "RA1") (pin "P$44") (pinfunction "44_P$44") (pintype "passive"))
    )
    (net (code "62") (name "Net-(RA2-11)") (class "Default")
      (node (ref "NFC0") (pin "5") (pinfunction "5_5") (pintype "passive"))
      (node (ref "RA2") (pin "P$11") (pinfunction "11_P$11") (pintype "passive"))
    )
    (net (code "63") (name "Net-(RA2-22)") (class "Default")
      (node (ref "NFC0") (pin "4") (pinfunction "4_4") (pintype "passive"))
      (node (ref "RA2") (pin "P$22") (pinfunction "22_P$22") (pintype "passive"))
    )
    (net (code "64") (name "Net-(RA2-33)") (class "Default")
      (node (ref "NFC0") (pin "3") (pinfunction "3_3") (pintype "passive"))
      (node (ref "RA2") (pin "P$33") (pinfunction "33_P$33") (pintype "passive"))
    )
    (net (code "65") (name "Net-(RA2-44)") (class "Default")
      (node (ref "NFC0") (pin "2") (pinfunction "2_2") (pintype "passive"))
      (node (ref "RA2") (pin "P$44") (pinfunction "44_P$44") (pintype "passive"))
    )
    (net (code "66") (name "Net-(RA3-33)") (class "Default")
      (node (ref "NFC1") (pin "7") (pinfunction "7_7") (pintype "passive"))
      (node (ref "RA3") (pin "P$33") (pinfunction "33_P$33") (pintype "passive"))
    )
    (net (code "67") (name "Net-(RA3-44)") (class "Default")
      (node (ref "NFC1") (pin "6") (pinfunction "6_6") (pintype "passive"))
      (node (ref "RA3") (pin "P$44") (pinfunction "44_P$44") (pintype "passive"))
    )
    (net (code "68") (name "Net-(RA4-11)") (class "Default")
      (node (ref "NFC1") (pin "5") (pinfunction "5_5") (pintype "passive"))
      (node (ref "RA4") (pin "P$11") (pinfunction "11_P$11") (pintype "passive"))
    )
    (net (code "69") (name "Net-(RA4-22)") (class "Default")
      (node (ref "NFC1") (pin "4") (pinfunction "4_4") (pintype "passive"))
      (node (ref "RA4") (pin "P$22") (pinfunction "22_P$22") (pintype "passive"))
    )
    (net (code "70") (name "Net-(RA4-33)") (class "Default")
      (node (ref "NFC1") (pin "3") (pinfunction "3_3") (pintype "passive"))
      (node (ref "RA4") (pin "P$33") (pinfunction "33_P$33") (pintype "passive"))
    )
    (net (code "71") (name "Net-(RA4-44)") (class "Default")
      (node (ref "NFC1") (pin "2") (pinfunction "2_2") (pintype "passive"))
      (node (ref "RA4") (pin "P$44") (pinfunction "44_P$44") (pintype "passive"))
    )
    (net (code "72") (name "Net-(RA8-11)") (class "Default")
      (node (ref "JP6") (pin "15") (pinfunction "15_15") (pintype "passive"))
      (node (ref "RA8") (pin "P$11") (pinfunction "11_P$11") (pintype "passive"))
    )
    (net (code "73") (name "Net-(RA8-22)") (class "Default")
      (node (ref "JP6") (pin "16") (pinfunction "16_16") (pintype "passive"))
      (node (ref "RA8") (pin "P$22") (pinfunction "22_P$22") (pintype "passive"))
    )
    (net (code "74") (name "Net-(RA8-33)") (class "Default")
      (node (ref "JP6") (pin "17") (pinfunction "17_17") (pintype "passive"))
      (node (ref "RA8") (pin "P$33") (pinfunction "33_P$33") (pintype "passive"))
    )
    (net (code "75") (name "Net-(RA8-44)") (class "Default")
      (node (ref "JP6") (pin "18") (pinfunction "18_18") (pintype "passive"))
      (node (ref "RA8") (pin "P$44") (pinfunction "44_P$44") (pintype "passive"))
    )
    (net (code "76") (name "Net-(RA9-11)") (class "Default")
      (node (ref "JP6") (pin "23") (pinfunction "23_23") (pintype "passive"))
      (node (ref "RA9") (pin "P$11") (pinfunction "11_P$11") (pintype "passive"))
    )
    (net (code "77") (name "Net-(RA9-22)") (class "Default")
      (node (ref "JP6") (pin "24") (pinfunction "24_24") (pintype "passive"))
      (node (ref "RA9") (pin "P$22") (pinfunction "22_P$22") (pintype "passive"))
    )
    (net (code "78") (name "Net-(RA9-33)") (class "Default")
      (node (ref "JP6") (pin "26") (pinfunction "26_26") (pintype "passive"))
      (node (ref "RA9") (pin "P$33") (pinfunction "33_P$33") (pintype "passive"))
    )
    (net (code "79") (name "Net-(RA10-11)") (class "Default")
      (node (ref "JP6") (pin "25") (pinfunction "25_25") (pintype "passive"))
      (node (ref "RA10") (pin "P$11") (pinfunction "11_P$11") (pintype "passive"))
    )
    (net (code "80") (name "Net-(RA10-22)") (class "Default")
      (node (ref "JP6") (pin "28") (pinfunction "28_28") (pintype "passive"))
      (node (ref "RA10") (pin "P$22") (pinfunction "22_P$22") (pintype "passive"))
    )
    (net (code "81") (name "Net-(RA10-33)") (class "Default")
      (node (ref "JP6") (pin "27") (pinfunction "27_27") (pintype "passive"))
      (node (ref "RA10") (pin "P$33") (pinfunction "33_P$33") (pintype "passive"))
    )
    (net (code "82") (name "Net-(U$1-AN)") (class "Default")
      (node (ref "R9") (pin "2") (pinfunction "2_2") (pintype "passive"))
      (node (ref "U$1") (pin "ANODE") (pinfunction "AN_ANODE") (pintype "input"))
    )
    (net (code "83") (name "Net-(U$2-AN)") (class "Default")
      (node (ref "R11") (pin "2") (pinfunction "2_2") (pintype "passive"))
      (node (ref "U$2") (pin "ANODE") (pinfunction "AN_ANODE") (pintype "input"))
    )
    (net (code "84") (name "Net-(U$3-AN)") (class "Default")
      (node (ref "R12") (pin "2") (pinfunction "2_2") (pintype "passive"))
      (node (ref "U$3") (pin "ANODE") (pinfunction "AN_ANODE") (pintype "input"))
    )
    (net (code "85") (name "Net-(U$23-PH1)") (class "Default")
      (node (ref "R3") (pin "2") (pinfunction "2_2") (pintype "passive"))
      (node (ref "U$23") (pin "6") (pinfunction "PH1_6") (pintype "bidirectional"))
    )
    (net (code "86") (name "OSC_IN") (class "Default")
      (node (ref "C13") (pin "1") (pinfunction "1_1") (pintype "passive"))
      (node (ref "U$23") (pin "5") (pinfunction "PH0_5") (pintype "bidirectional"))
      (node (ref "X1") (pin "0") (pinfunction "P$1_0") (pintype "bidirectional"))
    )
    (net (code "87") (name "OSC_OUT") (class "Default")
      (node (ref "C17") (pin "1") (pinfunction "1_1") (pintype "passive"))
      (node (ref "R3") (pin "1") (pinfunction "1_1") (pintype "passive"))
      (node (ref "X1") (pin "1") (pinfunction "P$2_1") (pintype "bidirectional"))
    )
    (net (code "88") (name "PRG_RX<") (class "Default")
      (node (ref "PWG") (pin "1") (pinfunction "1_1") (pintype "passive"))
      (node (ref "U$23") (pin "59") (pinfunction "PB7_59") (pintype "bidirectional"))
    )
    (net (code "89") (name "PRG_TX>") (class "Default")
      (node (ref "PWG") (pin "2") (pinfunction "2_2") (pintype "passive"))
      (node (ref "U$23") (pin "58") (pinfunction "PB6_58") (pintype "bidirectional"))
    )
    (net (code "90") (name "SCL") (class "Default")
      (node (ref "JP1") (pin "8") (pinfunction "8_8") (pintype "passive"))
    )
    (net (code "91") (name "SDA") (class "Default")
      (node (ref "JP1") (pin "7") (pinfunction "7_7") (pintype "passive"))
    )
    (net (code "92") (name "SOCK_A0") (class "Default")
      (node (ref "JP6") (pin "10") (pinfunction "10_10") (pintype "passive"))
      (node (ref "RA7") (pin "P$44") (pinfunction "44_P$44") (pintype "passive"))
    )
    (net (code "93") (name "SOCK_BACK") (class "Default")
      (node (ref "JP6") (pin "3") (pinfunction "3_3") (pintype "passive"))
      (node (ref "RA5") (pin "P$44") (pinfunction "44_P$44") (pintype "passive"))
    )
    (net (code "94") (name "SOCK_CLK") (class "Default")
      (node (ref "JP6") (pin "12") (pinfunction "12_12") (pintype "passive"))
      (node (ref "RA6") (pin "P$22") (pinfunction "22_P$22") (pintype "passive"))
    )
    (net (code "95") (name "SOCK_NCS1") (class "Default")
      (node (ref "JP6") (pin "9") (pinfunction "9_9") (pintype "passive"))
      (node (ref "RA7") (pin "P$33") (pinfunction "33_P$33") (pintype "passive"))
    )
    (net (code "96") (name "SOCK_NCS2") (class "Default")
      (node (ref "JP6") (pin "11") (pinfunction "11_11") (pintype "passive"))
      (node (ref "RA6") (pin "P$11") (pinfunction "11_P$11") (pintype "passive"))
    )
    (net (code "97") (name "SOCK_NRD") (class "Default")
      (node (ref "JP6") (pin "7") (pinfunction "7_7") (pintype "passive"))
      (node (ref "RA7") (pin "P$11") (pinfunction "11_P$11") (pintype "passive"))
    )
    (net (code "98") (name "SOCK_NRST") (class "Default")
      (node (ref "JP6") (pin "8") (pinfunction "8_8") (pintype "passive"))
      (node (ref "RA7") (pin "P$22") (pinfunction "22_P$22") (pintype "passive"))
    )
    (net (code "99") (name "SOCK_NWR") (class "Default")
      (node (ref "JP6") (pin "13") (pinfunction "13_13") (pintype "passive"))
      (node (ref "RA6") (pin "P$33") (pinfunction "33_P$33") (pintype "passive"))
    )
    (net (code "100") (name "SOCK_ROTA") (class "Default")
      (node (ref "JP6") (pin "2") (pinfunction "2_2") (pintype "passive"))
      (node (ref "RA5") (pin "P$11") (pinfunction "11_P$11") (pintype "passive"))
    )
    (net (code "101") (name "SOCK_ROTB") (class "Default")
      (node (ref "JP6") (pin "4") (pinfunction "4_4") (pintype "passive"))
      (node (ref "RA5") (pin "P$33") (pinfunction "33_P$33") (pintype "passive"))
    )
    (net (code "102") (name "SOCK_ROTSW") (class "Default")
      (node (ref "JP6") (pin "1") (pinfunction "1_1") (pintype "passive"))
      (node (ref "RA5") (pin "P$22") (pinfunction "22_P$22") (pintype "passive"))
    )
    (net (code "103") (name "SPI_CLK") (class "Default")
      (node (ref "RA2") (pin "P$4") (pinfunction "4_P$4") (pintype "passive"))
      (node (ref "RA4") (pin "P$4") (pinfunction "4_P$4") (pintype "passive"))
      (node (ref "RA8") (pin "P$2") (pinfunction "2_P$2") (pintype "passive"))
      (node (ref "SPI") (pin "3") (pinfunction "3_3") (pintype "passive"))
      (node (ref "U$23") (pin "21") (pinfunction "PA5_21") (pintype "bidirectional"))
      (node (ref "U$24") (pin "D5") (pinfunction "D5_D5") (pintype "bidirectional"))
    )
    (net (code "104") (name "SPI_MISO") (class "Default")
      (node (ref "RA2") (pin "P$3") (pinfunction "3_P$3") (pintype "passive"))
      (node (ref "RA4") (pin "P$3") (pinfunction "3_P$3") (pintype "passive"))
      (node (ref "U$23") (pin "22") (pinfunction "PA6_22") (pintype "bidirectional"))
      (node (ref "U$24") (pin "D6") (pinfunction "D6_D6") (pintype "bidirectional"))
    )
    (net (code "105") (name "SPI_MOSI") (class "Default")
      (node (ref "RA2") (pin "P$2") (pinfunction "2_P$2") (pintype "passive"))
      (node (ref "RA4") (pin "P$2") (pinfunction "2_P$2") (pintype "passive"))
      (node (ref "RA8") (pin "P$4") (pinfunction "4_P$4") (pintype "passive"))
      (node (ref "SPI") (pin "1") (pinfunction "1_1") (pintype "passive"))
      (node (ref "U$23") (pin "23") (pinfunction "PA7_23") (pintype "bidirectional"))
      (node (ref "U$24") (pin "D7") (pinfunction "D7_D7") (pintype "bidirectional"))
    )
    (net (code "106") (name "SWCLK") (class "Default")
      (node (ref "SWD1") (pin "2") (pinfunction "2_2") (pintype "passive"))
      (node (ref "U$23") (pin "49") (pinfunction "PA14_49") (pintype "bidirectional"))
    )
    (net (code "107") (name "SWDIO") (class "Default")
      (node (ref "SWD1") (pin "4") (pinfunction "4_4") (pintype "passive"))
      (node (ref "U$23") (pin "46") (pinfunction "PA13_46") (pintype "bidirectional"))
    )
    (net (code "108") (name "SWO") (class "Default")
      (node (ref "SWD1") (pin "6") (pinfunction "6_6") (pintype "passive"))
      (node (ref "U$23") (pin "55") (pinfunction "PB3_55") (pintype "bidirectional"))
    )
    (net (code "109") (name "USB12V") (class "Default")
      (node (ref "D1") (pin "A") (pinfunction "A_A") (pintype "passive"))
      (node (ref "D2") (pin "C") (pinfunction "C_C") (pintype "passive"))
      (node (ref "LM317") (pin "3") (pinfunction "3_3") (pintype "passive"))
      (node (ref "R1") (pin "2") (pinfunction "2_2") (pintype "passive"))
      (node (ref "SJ3") (pin "1") (pinfunction "1_1") (pintype "passive"))
      (node (ref "SJ5") (pin "2") (pinfunction "2_2") (pintype "passive"))
      (node (ref "SJ6") (pin "2") (pinfunction "2_2") (pintype "passive"))
    )
    (net (code "110") (name "USBGND") (class "Default")
      (node (ref "C3") (pin "2") (pinfunction "2_2") (pintype "passive"))
      (node (ref "C4") (pin "2") (pinfunction "2_2") (pintype "passive"))
      (node (ref "H3") (pin "B3,2") (pinfunction "MOUNT_B3,2") (pintype "passive"))
      (node (ref "JP1") (pin "10") (pinfunction "10_10") (pintype "passive"))
      (node (ref "JP1") (pin "5") (pinfunction "5_5") (pintype "passive"))
      (node (ref "JP1") (pin "6") (pinfunction "6_6") (pintype "passive"))
      (node (ref "JP2") (pin "1") (pinfunction "1_1") (pintype "passive"))
      (node (ref "JP2") (pin "3") (pinfunction "3_3") (pintype "passive"))
      (node (ref "JP2") (pin "5") (pinfunction "5_5") (pintype "passive"))
      (node (ref "R2") (pin "1") (pinfunction "A_1") (pintype "passive"))
      (node (ref "SJ4") (pin "1") (pinfunction "1_1") (pintype "passive"))
    )
    (net (code "111") (name "USBVBUS") (class "Default")
      (node (ref "C3") (pin "1") (pinfunction "1_1") (pintype "passive"))
      (node (ref "D1") (pin "C") (pinfunction "C_C") (pintype "passive"))
      (node (ref "LM317") (pin "1") (pinfunction "1_1") (pintype "passive"))
      (node (ref "SJ12") (pin "1") (pinfunction "1_1") (pintype "passive"))
      (node (ref "SJ13") (pin "1") (pinfunction "1_1") (pintype "passive"))
      (node (ref "SJ14") (pin "1") (pinfunction "1_1") (pintype "passive"))
      (node (ref "SJ5") (pin "1") (pinfunction "1_1") (pintype "passive"))
      (node (ref "SJ6") (pin "1") (pinfunction "1_1") (pintype "passive"))
      (node (ref "SJ8") (pin "2") (pinfunction "2_2") (pintype "passive"))
      (node (ref "SJ9") (pin "2") (pinfunction "2_2") (pintype "passive"))
    )
    (net (code "112") (name "V3.3") (class "Default")
      (node (ref "C1") (pin "1") (pinfunction "1_1") (pintype "passive"))
      (node (ref "C10") (pin "1") (pinfunction "1_1") (pintype "passive"))
      (node (ref "C11") (pin "1") (pinfunction "1_1") (pintype "passive"))
      (node (ref "C14") (pin "1") (pinfunction "1_1") (pintype "passive"))
      (node (ref "C15") (pin "1") (pinfunction "1_1") (pintype "passive"))
      (node (ref "C16") (pin "1") (pinfunction "1_1") (pintype "passive"))
      (node (ref "C6") (pin "1") (pinfunction "1_1") (pintype "passive"))
      (node (ref "C7") (pin "1") (pinfunction "1_1") (pintype "passive"))
      (node (ref "C8") (pin "1") (pinfunction "1_1") (pintype "passive"))
      (node (ref "JP6") (pin "14") (pinfunction "14_14") (pintype "passive"))
      (node (ref "JP6") (pin "5") (pinfunction "5_5") (pintype "passive"))
      (node (ref "NFC0") (pin "1") (pinfunction "1_1") (pintype "passive"))
      (node (ref "NFC1") (pin "1") (pinfunction "1_1") (pintype "passive"))
      (node (ref "R10") (pin "1") (pinfunction "1_1") (pintype "passive"))
      (node (ref "R11") (pin "1") (pinfunction "1_1") (pintype "passive"))
      (node (ref "SJ10") (pin "2") (pinfunction "2_2") (pintype "passive"))
      (node (ref "SWD1") (pin "1") (pinfunction "1_1") (pintype "passive"))
      (node (ref "U$15") (pin "VOUT") (pinfunction "VO_VOUT") (pintype "output"))
      (node (ref "U$15") (pin "VOUTB") (pinfunction "BODY_VOUTB") (pintype "open_collector"))
      (node (ref "U$21") (pin "VCC") (pinfunction "VCC_VCC") (pintype "power_in"))
      (node (ref "U$22") (pin "VCC") (pinfunction "VCC_VCC") (pintype "power_in"))
      (node (ref "U$23") (pin "1") (pinfunction "1:VBAT_1") (pintype "bidirectional"))
      (node (ref "U$23") (pin "13") (pinfunction "13:VDDA_13") (pintype "bidirectional"))
      (node (ref "U$23") (pin "19") (pinfunction "19:VDD_19") (pintype "bidirectional"))
      (node (ref "U$23") (pin "32") (pinfunction "32:VDD_32") (pintype "bidirectional"))
      (node (ref "U$23") (pin "48") (pinfunction "48:VDD_48") (pintype "bidirectional"))
      (node (ref "U$23") (pin "64") (pinfunction "64:VDD_64") (pintype "bidirectional"))
      (node (ref "U$24") (pin "V3.3") (pinfunction "V3.3_V3.3") (pintype "bidirectional"))
      (node (ref "U$24") (pin "V3.3@1") (pinfunction "V3.3_V3.3@1") (pintype "bidirectional"))
      (node (ref "U$24") (pin "V3.3@2") (pinfunction "V3.3_V3.3@2") (pintype "bidirectional"))
      (node (ref "U1") (pin "23") (pinfunction "VCCB_2_23") (pintype "power_in"))
      (node (ref "U1") (pin "24") (pinfunction "VCCB_24") (pintype "power_in"))
    )
    (net (code "113") (name "V5") (class "Default")
      (node (ref "C5") (pin "1") (pinfunction "1_1") (pintype "passive"))
      (node (ref "C9") (pin "1") (pinfunction "1_1") (pintype "passive"))
      (node (ref "JP6") (pin "20") (pinfunction "20_20") (pintype "passive"))
      (node (ref "JP6") (pin "21") (pinfunction "21_21") (pintype "passive"))
      (node (ref "JP6") (pin "30") (pinfunction "30_30") (pintype "passive"))
      (node (ref "NFC0") (pin "9") (pinfunction "9_9") (pintype "passive"))
      (node (ref "NFC1") (pin "9") (pinfunction "9_9") (pintype "passive"))
      (node (ref "R12") (pin "1") (pinfunction "1_1") (pintype "passive"))
      (node (ref "SJ11") (pin "2") (pinfunction "2_2") (pintype "passive"))
      (node (ref "U$13") (pin "16") (pinfunction "VCC1_16") (pintype "bidirectional"))
      (node (ref "U$15") (pin "VIN") (pinfunction "VI_VIN") (pintype "input"))
      (node (ref "U$16") (pin "VO") (pinfunction "P$3_VO") (pintype "output"))
      (node (ref "U$24") (pin "V5") (pinfunction "V5_V5") (pintype "bidirectional"))
      (node (ref "U1") (pin "1") (pinfunction "VCCA_1") (pintype "power_in"))
    )
    (net (code "114") (name "V12") (class "Default")
      (node (ref "C2") (pin "1") (pinfunction "1_1") (pintype "passive"))
      (node (ref "J2") (pin "3") (pinfunction "3_3") (pintype "passive"))
      (node (ref "SJ3") (pin "2") (pinfunction "2_2") (pintype "passive"))
      (node (ref "U$13") (pin "8") (pinfunction "VCC2_8") (pintype "bidirectional"))
      (node (ref "U$16") (pin "VI") (pinfunction "P$1_VI") (pintype "input"))
    )
    (net (code "115") (name "VADJ") (class "Default")
      (node (ref "C4") (pin "1") (pinfunction "1_1") (pintype "passive"))
      (node (ref "D2") (pin "A") (pinfunction "A_A") (pintype "passive"))
      (node (ref "LM317") (pin "2") (pinfunction "2_2") (pintype "passive"))
      (node (ref "R1") (pin "1") (pinfunction "1_1") (pintype "passive"))
      (node (ref "R2") (pin "2") (pinfunction "S_2") (pintype "passive"))
    )
    (net (code "116") (name "VBUS") (class "Default")
      (node (ref "JP2") (pin "2") (pinfunction "2_2") (pintype "passive"))
      (node (ref "JP2") (pin "4") (pinfunction "4_4") (pintype "passive"))
      (node (ref "SJ12") (pin "2") (pinfunction "2_2") (pintype "passive"))
    )
    (net (code "117") (name "VBUS_A") (class "Default")
      (node (ref "JP1") (pin "4") (pinfunction "4_4") (pintype "passive"))
      (node (ref "SJ14") (pin "2") (pinfunction "2_2") (pintype "passive"))
    )
    (net (code "118") (name "VCAP") (class "Default")
      (node (ref "C12") (pin "1") (pinfunction "1_1") (pintype "passive"))
      (node (ref "U$23") (pin "30") (pinfunction "30:VCAP_30") (pintype "bidirectional"))
    )
    (net (code "119") (name "VCONN") (class "Default")
      (node (ref "JP2") (pin "6") (pinfunction "6_6") (pintype "passive"))
      (node (ref "SJ13") (pin "2") (pinfunction "2_2") (pintype "passive"))
    )
    (net (code "120") (name "VCONNA") (class "Default")
      (node (ref "JP1") (pin "1") (pinfunction "1_1") (pintype "passive"))
      (node (ref "SJ9") (pin "1") (pinfunction "1_1") (pintype "passive"))
    )
    (net (code "121") (name "VDD") (class "Default")
      (node (ref "JP1") (pin "12") (pinfunction "12_12") (pintype "passive"))
      (node (ref "SJ8") (pin "1") (pinfunction "1_1") (pintype "passive"))
    )
    (net (code "122") (name "VLT_DIR") (class "Default")
      (node (ref "U$23") (pin "36") (pinfunction "PB15_36") (pintype "bidirectional"))
      (node (ref "U1") (pin "2") (pinfunction "DIR_2") (pintype "input"))
    )
    (net (code "123") (name "VPU") (class "Default")
      (node (ref "JP1") (pin "11") (pinfunction "11_11") (pintype "passive"))
    )
    (net (code "124") (name "V_PULLUP") (class "Default")
      (node (ref "JP1") (pin "2") (pinfunction "2_2") (pintype "passive"))
    )
    (net (code "125") (name "WIFI_CS") (class "Default")
      (node (ref "U$23") (pin "28") (pinfunction "PB2_28") (pintype "bidirectional"))
      (node (ref "U$24") (pin "D8") (pinfunction "D8_D8") (pintype "bidirectional"))
    )
    (net (code "126") (name "WIFI_GPIO") (class "Default")
      (node (ref "U$24") (pin "D1") (pinfunction "D1_D1") (pintype "bidirectional"))
    )
    (net (code "127") (name "WIFI_IRQ") (class "Default")
      (node (ref "U$23") (pin "29") (pinfunction "PB10_29") (pintype "bidirectional"))
      (node (ref "U$24") (pin "D0") (pinfunction "D0_D0") (pintype "bidirectional"))
    )
    (net (code "128") (name "unconnected-(JP1-Pad3)") (class "Default")
      (node (ref "JP1") (pin "3") (pinfunction "3_3") (pintype "passive"))
    )
    (net (code "129") (name "unconnected-(JP6-Pad29)") (class "Default")
      (node (ref "JP6") (pin "29") (pinfunction "29_29") (pintype "passive"))
    )
    (net (code "130") (name "unconnected-(LCD-Pad1)") (class "Default")
      (node (ref "LCD") (pin "1") (pinfunction "1_1") (pintype "passive"))
    )
    (net (code "131") (name "unconnected-(R2-E-Pad3)") (class "Default")
      (node (ref "R2") (pin "3") (pinfunction "E_3") (pintype "passive"))
    )
    (net (code "132") (name "unconnected-(RA1-1-PadP$1)") (class "Default")
      (node (ref "RA1") (pin "P$1") (pinfunction "1_P$1") (pintype "passive"))
    )
    (net (code "133") (name "unconnected-(RA1-2-PadP$2)") (class "Default")
      (node (ref "RA1") (pin "P$2") (pinfunction "2_P$2") (pintype "passive"))
    )
    (net (code "134") (name "unconnected-(RA1-11-PadP$11)") (class "Default")
      (node (ref "RA1") (pin "P$11") (pinfunction "11_P$11") (pintype "passive"))
    )
    (net (code "135") (name "unconnected-(RA1-22-PadP$22)") (class "Default")
      (node (ref "RA1") (pin "P$22") (pinfunction "22_P$22") (pintype "passive"))
    )
    (net (code "136") (name "unconnected-(RA3-1-PadP$1)") (class "Default")
      (node (ref "RA3") (pin "P$1") (pinfunction "1_P$1") (pintype "passive"))
    )
    (net (code "137") (name "unconnected-(RA3-2-PadP$2)") (class "Default")
      (node (ref "RA3") (pin "P$2") (pinfunction "2_P$2") (pintype "passive"))
    )
    (net (code "138") (name "unconnected-(RA3-11-PadP$11)") (class "Default")
      (node (ref "RA3") (pin "P$11") (pinfunction "11_P$11") (pintype "passive"))
    )
    (net (code "139") (name "unconnected-(RA3-22-PadP$22)") (class "Default")
      (node (ref "RA3") (pin "P$22") (pinfunction "22_P$22") (pintype "passive"))
    )
    (net (code "140") (name "unconnected-(RA6-4-PadP$4)") (class "Default")
      (node (ref "RA6") (pin "P$4") (pinfunction "4_P$4") (pintype "passive"))
    )
    (net (code "141") (name "unconnected-(RA6-44-PadP$44)") (class "Default")
      (node (ref "RA6") (pin "P$44") (pinfunction "44_P$44") (pintype "passive"))
    )
    (net (code "142") (name "unconnected-(RA9-4-PadP$4)") (class "Default")
      (node (ref "RA9") (pin "P$4") (pinfunction "4_P$4") (pintype "passive"))
    )
    (net (code "143") (name "unconnected-(RA9-44-PadP$44)") (class "Default")
      (node (ref "RA9") (pin "P$44") (pinfunction "44_P$44") (pintype "passive"))
    )
    (net (code "144") (name "unconnected-(RA10-4-PadP$4)") (class "Default")
      (node (ref "RA10") (pin "P$4") (pinfunction "4_P$4") (pintype "passive"))
    )
    (net (code "145") (name "unconnected-(RA10-44-PadP$44)") (class "Default")
      (node (ref "RA10") (pin "P$44") (pinfunction "44_P$44") (pintype "passive"))
    )
    (net (code "146") (name "unconnected-(U$1-CA-PadCATHODE)") (class "Default")
      (node (ref "U$1") (pin "CATHODE") (pinfunction "CA_CATHODE") (pintype "output"))
    )
    (net (code "147") (name "unconnected-(U$24-PadA0)") (class "Default")
      (node (ref "U$24") (pin "A0") (pinfunction "A0_A0") (pintype "bidirectional"))
    )
    (net (code "148") (name "unconnected-(U$24-PadCLK)") (class "Default")
      (node (ref "U$24") (pin "CLK") (pinfunction "CLK_CLK") (pintype "bidirectional"))
    )
    (net (code "149") (name "unconnected-(U$24-PadCMD)") (class "Default")
      (node (ref "U$24") (pin "CMD") (pinfunction "CMD_CMD") (pintype "bidirectional"))
    )
    (net (code "150") (name "unconnected-(U$24-PadD2)") (class "Default")
      (node (ref "U$24") (pin "D2") (pinfunction "D2_D2") (pintype "bidirectional"))
    )
    (net (code "151") (name "unconnected-(U$24-PadD3)") (class "Default")
      (node (ref "U$24") (pin "D3") (pinfunction "D3_D3") (pintype "bidirectional"))
    )
    (net (code "152") (name "unconnected-(U$24-PadD4)") (class "Default")
      (node (ref "U$24") (pin "D4") (pinfunction "D4_D4") (pintype "bidirectional"))
    )
    (net (code "153") (name "unconnected-(U$24-PadEN)") (class "Default")
      (node (ref "U$24") (pin "EN") (pinfunction "EN_EN") (pintype "bidirectional"))
    )
    (net (code "154") (name "unconnected-(U$24-PadRST)") (class "Default")
      (node (ref "U$24") (pin "RST") (pinfunction "RST_RST") (pintype "bidirectional"))
    )
    (net (code "155") (name "unconnected-(U$24-PadRSV)") (class "Default")
      (node (ref "U$24") (pin "RSV") (pinfunction "RSV_RSV") (pintype "bidirectional"))
    )
    (net (code "156") (name "unconnected-(U$24-PadRX)") (class "Default")
      (node (ref "U$24") (pin "RX") (pinfunction "RX_RX") (pintype "bidirectional"))
    )
    (net (code "157") (name "unconnected-(U$24-PadSD0)") (class "Default")
      (node (ref "U$24") (pin "SD0") (pinfunction "SD0_SD0") (pintype "bidirectional"))
    )
    (net (code "158") (name "unconnected-(U$24-PadSD1)") (class "Default")
      (node (ref "U$24") (pin "SD1") (pinfunction "SD1_SD1") (pintype "bidirectional"))
    )
    (net (code "159") (name "unconnected-(U$24-PadSD2)") (class "Default")
      (node (ref "U$24") (pin "SD2") (pinfunction "SD2_SD2") (pintype "bidirectional"))
    )
    (net (code "160") (name "unconnected-(U$24-PadSD3)") (class "Default")
      (node (ref "U$24") (pin "SD3") (pinfunction "SD3_SD3") (pintype "bidirectional"))
    )
    (net (code "161") (name "unconnected-(U$24-PadTX)") (class "Default")
      (node (ref "U$24") (pin "TX") (pinfunction "TX_TX") (pintype "bidirectional"))
    )
    (net (code "162") (name "unconnected-(U$24-RSV-PadRSV@1)") (class "Default")
      (node (ref "U$24") (pin "RSV@1") (pinfunction "RSV_RSV@1") (pintype "bidirectional"))
    )
    (net (code "163") (name "unconnected-(U1-A6-Pad9)") (class "Default")
      (node (ref "U1") (pin "9") (pinfunction "A6_9") (pintype "bidirectional"))
    )
    (net (code "164") (name "unconnected-(U1-A7-Pad10)") (class "Default")
      (node (ref "U1") (pin "10") (pinfunction "A7_10") (pintype "bidirectional"))
    )
    (net (code "165") (name "unconnected-(U1-B6-Pad15)") (class "Default")
      (node (ref "U1") (pin "15") (pinfunction "B6_15") (pintype "bidirectional"))
    )
    (net (code "166") (name "unconnected-(U1-B7-Pad14)") (class "Default")
      (node (ref "U1") (pin "14") (pinfunction "B7_14") (pintype "bidirectional"))
    )
    (net (code "167") (name "unconnected-(U2-Pad2)") (class "Default")
      (node (ref "U2") (pin "2") (pinfunction "2_2") (pintype "passive"))
    )
    (net (code "168") (name "unconnected-(U2-Pad4)") (class "Default")
      (node (ref "U2") (pin "4") (pinfunction "4_4") (pintype "passive"))
    )
  )
)
